# SCH_IR_BEam_Sensor_2023-01-03.net
KiCad netlist of a schematic drawn in EasyEDA
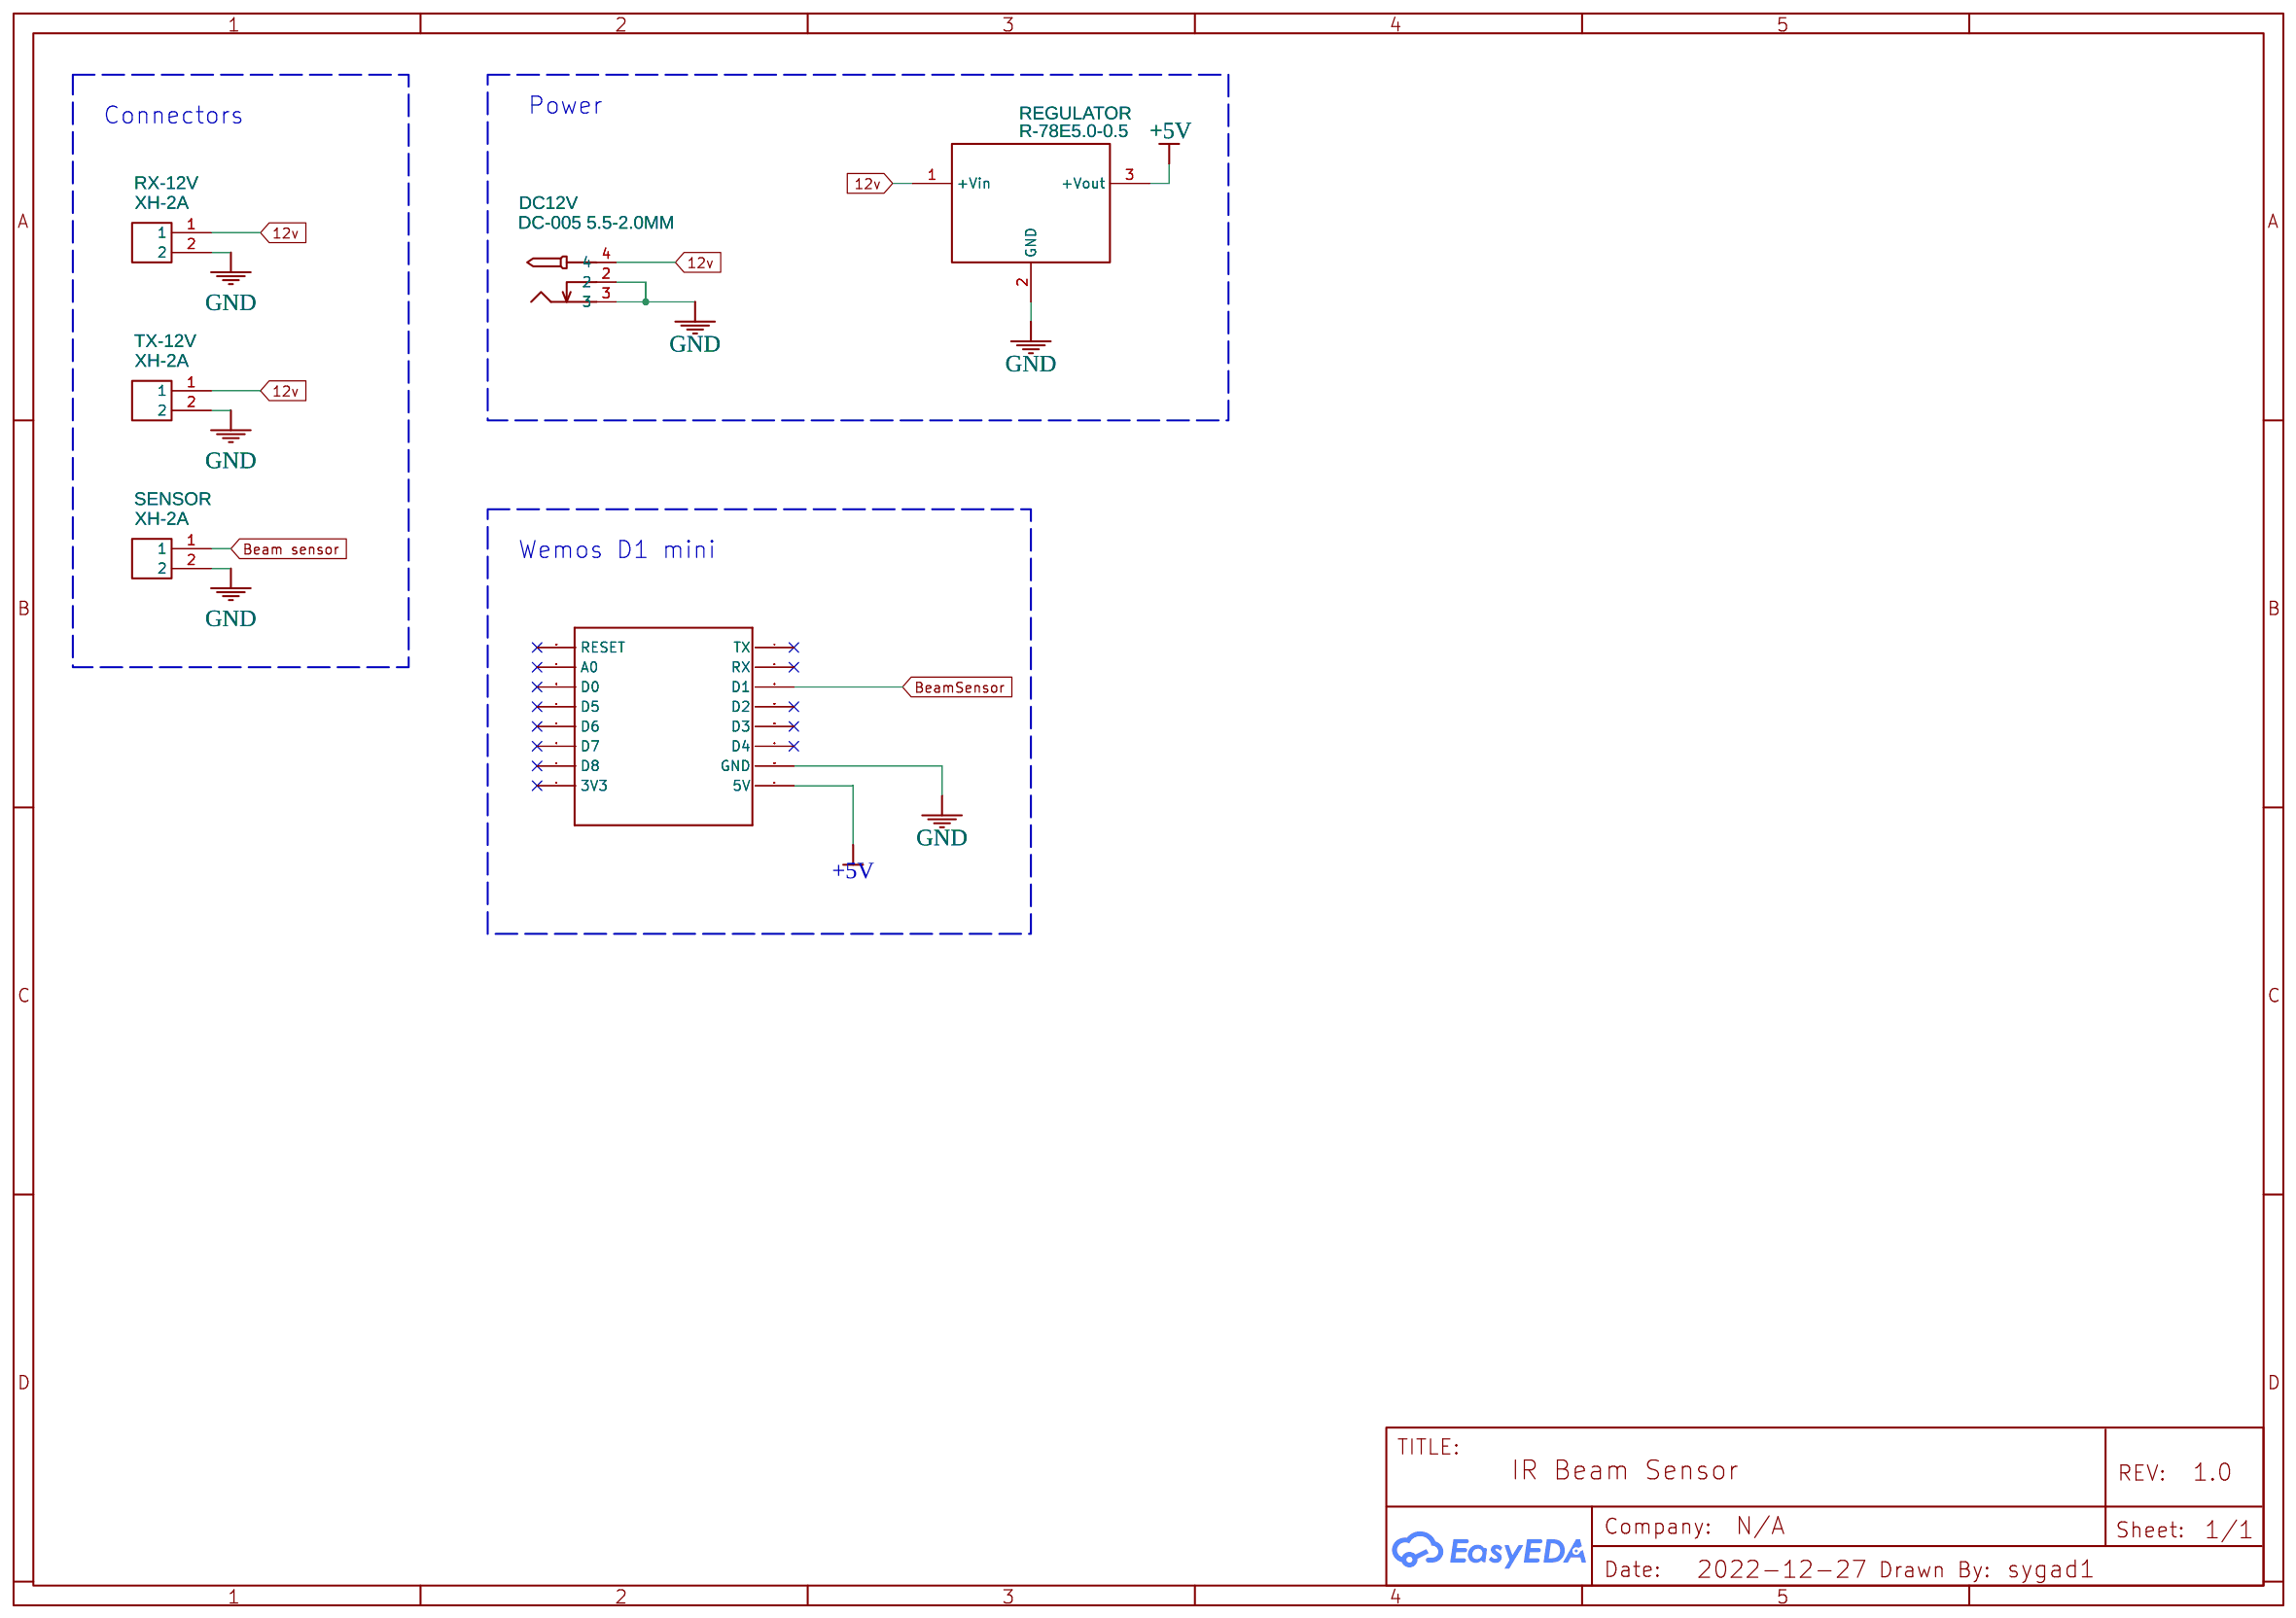
[diagram p0: schematic sheet]

(export (version "E")
  (design (tool "Eeschema 10.0.6"))
  (components
    (comp (ref "DC12V")
      (value "DC-005 5.5-2.0MM")
      (fields (field (name "BOM_Supplier Part") "C16214"))
      (libsource (lib "") (part "DC-005 5.5-2.0MM"))
    )
    (comp (ref "REGULATOR")
      (value "R-78E5.0-0.5")
      (fields (field (name "BOM_Supplier Part") "945-1648-5-ND"))
      (libsource (lib "") (part "R-78E5.0-0.5"))
    )
    (comp (ref "RX-12V")
      (value "XH-2A")
      (fields (field (name "BOM_Supplier Part") "C20079"))
      (libsource (lib "") (part "XH-2A_2"))
    )
    (comp (ref "SENSOR")
      (value "XH-2A")
      (fields (field (name "BOM_Supplier Part") "C20079"))
      (libsource (lib "") (part "XH-2A"))
    )
    (comp (ref "TX-12V")
      (value "XH-2A")
      (fields (field (name "BOM_Supplier Part") "C20079"))
      (libsource (lib "") (part "XH-2A_1"))
    )
    (comp (ref "WEMOS1") (value "WEMOS-D1-MINI") (libsource (lib "") (part "WEMOS-D1-MINI")))
  )
  (nets
    (net (code "1") (name "+5V") (class "Default")
      (node (ref "REGULATOR") (pin "3") (pinfunction "+Vout_3") (pintype "unspecified"))
      (node (ref "WEMOS1") (pin "5V") (pinfunction "5V_5V") (pintype "bidirectional"))
    )
    (net (code "2") (name "12v") (class "Default")
      (node (ref "DC12V") (pin "4") (pinfunction "4_4") (pintype "unspecified"))
      (node (ref "REGULATOR") (pin "1") (pinfunction "+Vin_1") (pintype "unspecified"))
      (node (ref "RX-12V") (pin "1") (pinfunction "1_1") (pintype "unspecified"))
      (node (ref "TX-12V") (pin "1") (pinfunction "1_1") (pintype "unspecified"))
    )
    (net (code "3") (name "Beam sensor") (class "Default")
      (node (ref "SENSOR") (pin "1") (pinfunction "1_1") (pintype "unspecified"))
    )
    (net (code "4") (name "BeamSensor") (class "Default")
      (node (ref "WEMOS1") (pin "D1") (pinfunction "D1_D1") (pintype "bidirectional"))
    )
    (net (code "5") (name "GND") (class "Default")
      (node (ref "DC12V") (pin "2") (pinfunction "2_2") (pintype "unspecified"))
      (node (ref "DC12V") (pin "3") (pinfunction "3_3") (pintype "unspecified"))
      (node (ref "REGULATOR") (pin "2") (pinfunction "GND_2") (pintype "unspecified"))
      (node (ref "RX-12V") (pin "2") (pinfunction "2_2") (pintype "unspecified"))
      (node (ref "SENSOR") (pin "2") (pinfunction "2_2") (pintype "unspecified"))
      (node (ref "TX-12V") (pin "2") (pinfunction "2_2") (pintype "unspecified"))
      (node (ref "WEMOS1") (pin "GND") (pinfunction "GND_GND") (pintype "bidirectional"))
    )
    (net (code "6") (name "unconnected-(WEMOS1-Pad3V3)") (class "Default")
      (node (ref "WEMOS1") (pin "3V3") (pinfunction "3V3_3V3") (pintype "bidirectional+no_connect"))
    )
    (net (code "7") (name "unconnected-(WEMOS1-PadA0)") (class "Default")
      (node (ref "WEMOS1") (pin "A0") (pinfunction "A0_A0") (pintype "bidirectional+no_connect"))
    )
    (net (code "8") (name "unconnected-(WEMOS1-PadD0)") (class "Default")
      (node (ref "WEMOS1") (pin "D0") (pinfunction "D0_D0") (pintype "bidirectional+no_connect"))
    )
    (net (code "9") (name "unconnected-(WEMOS1-PadD2)") (class "Default")
      (node (ref "WEMOS1") (pin "D2") (pinfunction "D2_D2") (pintype "bidirectional+no_connect"))
    )
    (net (code "10") (name "unconnected-(WEMOS1-PadD3)") (class "Default")
      (node (ref "WEMOS1") (pin "D3") (pinfunction "D3_D3") (pintype "bidirectional+no_connect"))
    )
    (net (code "11") (name "unconnected-(WEMOS1-PadD4)") (class "Default")
      (node (ref "WEMOS1") (pin "D4") (pinfunction "D4_D4") (pintype "bidirectional+no_connect"))
    )
    (net (code "12") (name "unconnected-(WEMOS1-PadD5)") (class "Default")
      (node (ref "WEMOS1") (pin "D5") (pinfunction "D5_D5") (pintype "bidirectional+no_connect"))
    )
    (net (code "13") (name "unconnected-(WEMOS1-PadD6)") (class "Default")
      (node (ref "WEMOS1") (pin "D6") (pinfunction "D6_D6") (pintype "bidirectional+no_connect"))
    )
    (net (code "14") (name "unconnected-(WEMOS1-PadD7)") (class "Default")
      (node (ref "WEMOS1") (pin "D7") (pinfunction "D7_D7") (pintype "bidirectional+no_connect"))
    )
    (net (code "15") (name "unconnected-(WEMOS1-PadD8)") (class "Default")
      (node (ref "WEMOS1") (pin "D8") (pinfunction "D8_D8") (pintype "bidirectional+no_connect"))
    )
    (net (code "16") (name "unconnected-(WEMOS1-PadRESET)") (class "Default")
      (node (ref "WEMOS1") (pin "RESET") (pinfunction "RESET_RESET") (pintype "bidirectional+no_connect"))
    )
    (net (code "17") (name "unconnected-(WEMOS1-PadRX)") (class "Default")
      (node (ref "WEMOS1") (pin "RX") (pinfunction "RX_RX") (pintype "bidirectional+no_connect"))
    )
    (net (code "18") (name "unconnected-(WEMOS1-PadTX)") (class "Default")
      (node (ref "WEMOS1") (pin "TX") (pinfunction "TX_TX") (pintype "bidirectional+no_connect"))
    )
  )
)
